# rpi-i2c.net
KiCad netlist of a schematic drawn in EAGLE
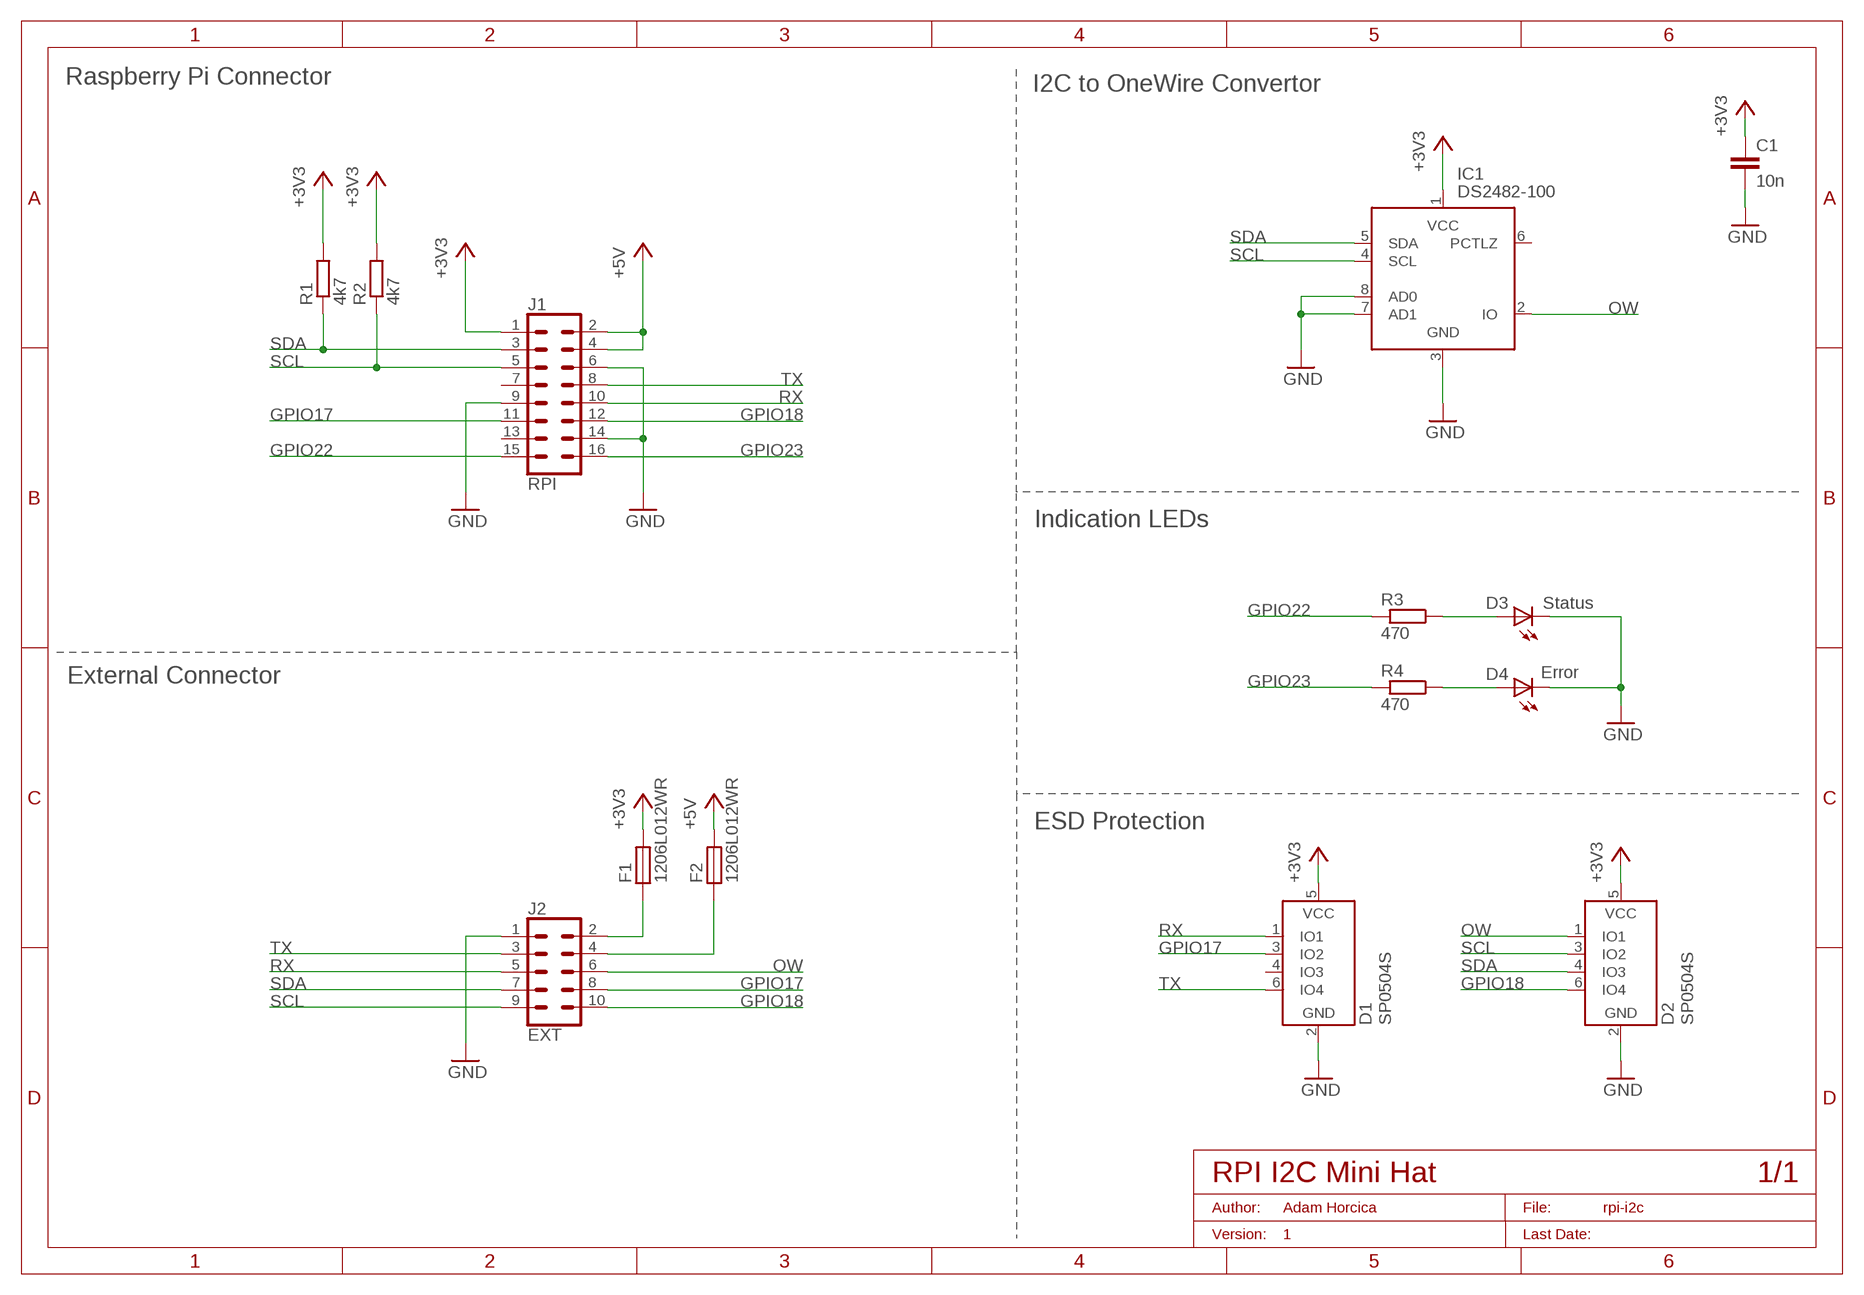
[diagram p0: schematic, sheet 1]

(export (version "E")
  (design (tool "Eeschema 10.0.6"))
  (components
    (comp (ref "C1")
      (value "10n")
      (footprint "eagle-import:C0805")
      (libsource (lib "eagle-import") (part "C-EUC0805"))
    )
    (comp (ref "D1")
      (value "SP0504S")
      (footprint "eagle-import:SOT23-6")
      (libsource (lib "eagle-import") (part "SP0504S"))
    )
    (comp (ref "D2")
      (value "SP0504S")
      (footprint "eagle-import:SOT23-6")
      (libsource (lib "eagle-import") (part "SP0504S"))
    )
    (comp (ref "D3")
      (value "LEDCHIPLED_0805")
      (footprint "eagle-import:CHIPLED_0805")
      (libsource (lib "eagle-import") (part "LEDCHIPLED_0805"))
    )
    (comp (ref "D4")
      (value "LEDCHIPLED_0805")
      (footprint "eagle-import:CHIPLED_0805")
      (libsource (lib "eagle-import") (part "LEDCHIPLED_0805"))
    )
    (comp (ref "F1")
      (value "1206L012WR")
      (footprint "eagle-import:C1206K")
      (fields (field (name "OC_FARNELL") "1596988"))
      (libsource (lib "eagle-import") (part "PTC1206L075/13.2WR"))
    )
    (comp (ref "F2")
      (value "1206L012WR")
      (footprint "eagle-import:C1206K")
      (fields (field (name "OC_FARNELL") "1596988"))
      (libsource (lib "eagle-import") (part "PTC1206L075/13.2WR"))
    )
    (comp (ref "IC1")
      (value "DS2482-100")
      (footprint "eagle-import:SO08")
      (libsource (lib "eagle-import") (part "DS2482-100"))
    )
    (comp (ref "J1")
      (value "RPI")
      (footprint "eagle-import:2X8-INVERSE")
      (libsource (lib "eagle-import") (part "CONN_08X2I"))
    )
    (comp (ref "J2")
      (value "EXT")
      (footprint "eagle-import:30310-5002HB")
      (libsource (lib "eagle-import") (part "CONN_05X2"))
    )
    (comp (ref "R1")
      (value "4k7")
      (footprint "eagle-import:R0603")
      (libsource (lib "eagle-import") (part "R-EU_R0603"))
    )
    (comp (ref "R2")
      (value "4k7")
      (footprint "eagle-import:R0603")
      (libsource (lib "eagle-import") (part "R-EU_R0603"))
    )
    (comp (ref "R3")
      (value "470")
      (footprint "eagle-import:R0603")
      (libsource (lib "eagle-import") (part "R-EU_R0603"))
    )
    (comp (ref "R4")
      (value "470")
      (footprint "eagle-import:R0603")
      (libsource (lib "eagle-import") (part "R-EU_R0603"))
    )
  )
  (nets
    (net (code "1") (name "+3V3") (class "Default")
      (node (ref "C1") (pin "1") (pinfunction "1_1") (pintype "passive"))
      (node (ref "D1") (pin "5") (pinfunction "VCC_5") (pintype "bidirectional"))
      (node (ref "D2") (pin "5") (pinfunction "VCC_5") (pintype "bidirectional"))
      (node (ref "F1") (pin "2") (pinfunction "2_2") (pintype "passive"))
      (node (ref "IC1") (pin "1") (pinfunction "VCC_1") (pintype "bidirectional"))
      (node (ref "J1") (pin "1") (pinfunction "1_1") (pintype "passive"))
      (node (ref "R1") (pin "2") (pinfunction "2_2") (pintype "passive"))
      (node (ref "R2") (pin "2") (pinfunction "2_2") (pintype "passive"))
    )
    (net (code "2") (name "+5V") (class "Default")
      (node (ref "F2") (pin "2") (pinfunction "2_2") (pintype "passive"))
      (node (ref "J1") (pin "2") (pinfunction "2_2") (pintype "passive"))
      (node (ref "J1") (pin "4") (pinfunction "4_4") (pintype "passive"))
    )
    (net (code "3") (name "/GPIO17") (class "Default")
      (node (ref "D1") (pin "3") (pinfunction "IO2_3") (pintype "bidirectional"))
      (node (ref "J1") (pin "11") (pinfunction "11_11") (pintype "passive"))
      (node (ref "J2") (pin "8") (pinfunction "8_8") (pintype "passive"))
    )
    (net (code "4") (name "/GPIO18") (class "Default")
      (node (ref "D2") (pin "6") (pinfunction "IO4_6") (pintype "bidirectional"))
      (node (ref "J1") (pin "12") (pinfunction "12_12") (pintype "passive"))
      (node (ref "J2") (pin "10") (pinfunction "10_10") (pintype "passive"))
    )
    (net (code "5") (name "/GPIO22") (class "Default")
      (node (ref "J1") (pin "15") (pinfunction "15_15") (pintype "passive"))
      (node (ref "R3") (pin "2") (pinfunction "2_2") (pintype "passive"))
    )
    (net (code "6") (name "/GPIO23") (class "Default")
      (node (ref "J1") (pin "16") (pinfunction "16_16") (pintype "passive"))
      (node (ref "R4") (pin "2") (pinfunction "2_2") (pintype "passive"))
    )
    (net (code "7") (name "/OW") (class "Default")
      (node (ref "D2") (pin "1") (pinfunction "IO1_1") (pintype "bidirectional"))
      (node (ref "IC1") (pin "2") (pinfunction "IO_2") (pintype "bidirectional"))
      (node (ref "J2") (pin "6") (pinfunction "6_6") (pintype "passive"))
    )
    (net (code "8") (name "/RX") (class "Default")
      (node (ref "D1") (pin "1") (pinfunction "IO1_1") (pintype "bidirectional"))
      (node (ref "J1") (pin "10") (pinfunction "10_10") (pintype "passive"))
      (node (ref "J2") (pin "5") (pinfunction "5_5") (pintype "passive"))
    )
    (net (code "9") (name "/SCL") (class "Default")
      (node (ref "D2") (pin "3") (pinfunction "IO2_3") (pintype "bidirectional"))
      (node (ref "IC1") (pin "4") (pinfunction "SCL_4") (pintype "bidirectional"))
      (node (ref "J1") (pin "5") (pinfunction "5_5") (pintype "passive"))
      (node (ref "J2") (pin "9") (pinfunction "9_9") (pintype "passive"))
      (node (ref "R2") (pin "1") (pinfunction "1_1") (pintype "passive"))
    )
    (net (code "10") (name "/SDA") (class "Default")
      (node (ref "D2") (pin "4") (pinfunction "IO3_4") (pintype "bidirectional"))
      (node (ref "IC1") (pin "5") (pinfunction "SDA_5") (pintype "bidirectional"))
      (node (ref "J1") (pin "3") (pinfunction "3_3") (pintype "passive"))
      (node (ref "J2") (pin "7") (pinfunction "7_7") (pintype "passive"))
      (node (ref "R1") (pin "1") (pinfunction "1_1") (pintype "passive"))
    )
    (net (code "11") (name "/TX") (class "Default")
      (node (ref "D1") (pin "6") (pinfunction "IO4_6") (pintype "bidirectional"))
      (node (ref "J1") (pin "8") (pinfunction "8_8") (pintype "passive"))
      (node (ref "J2") (pin "3") (pinfunction "3_3") (pintype "passive"))
    )
    (net (code "12") (name "GND") (class "Default")
      (node (ref "C1") (pin "2") (pinfunction "2_2") (pintype "passive"))
      (node (ref "D1") (pin "2") (pinfunction "GND_2") (pintype "bidirectional"))
      (node (ref "D2") (pin "2") (pinfunction "GND_2") (pintype "bidirectional"))
      (node (ref "D3") (pin "C") (pinfunction "C_C") (pintype "passive"))
      (node (ref "D4") (pin "C") (pinfunction "C_C") (pintype "passive"))
      (node (ref "IC1") (pin "3") (pinfunction "GND_3") (pintype "bidirectional"))
      (node (ref "IC1") (pin "7") (pinfunction "AD1_7") (pintype "bidirectional"))
      (node (ref "IC1") (pin "8") (pinfunction "AD0_8") (pintype "bidirectional"))
      (node (ref "J1") (pin "14") (pinfunction "14_14") (pintype "passive"))
      (node (ref "J1") (pin "6") (pinfunction "6_6") (pintype "passive"))
      (node (ref "J1") (pin "9") (pinfunction "9_9") (pintype "passive"))
      (node (ref "J2") (pin "1") (pinfunction "1_1") (pintype "passive"))
    )
    (net (code "13") (name "Net-(D3-PadA)") (class "Default")
      (node (ref "D3") (pin "A") (pinfunction "A_A") (pintype "passive"))
      (node (ref "R3") (pin "1") (pinfunction "1_1") (pintype "passive"))
    )
    (net (code "14") (name "Net-(D4-PadA)") (class "Default")
      (node (ref "D4") (pin "A") (pinfunction "A_A") (pintype "passive"))
      (node (ref "R4") (pin "1") (pinfunction "1_1") (pintype "passive"))
    )
    (net (code "15") (name "Net-(F1-Pad1)") (class "Default")
      (node (ref "F1") (pin "1") (pinfunction "1_1") (pintype "passive"))
      (node (ref "J2") (pin "2") (pinfunction "2_2") (pintype "passive"))
    )
    (net (code "16") (name "Net-(F2-Pad1)") (class "Default")
      (node (ref "F2") (pin "1") (pinfunction "1_1") (pintype "passive"))
      (node (ref "J2") (pin "4") (pinfunction "4_4") (pintype "passive"))
    )
    (net (code "17") (name "unconnected-(D1-IO3-Pad4)") (class "Default")
      (node (ref "D1") (pin "4") (pinfunction "IO3_4") (pintype "bidirectional"))
    )
    (net (code "18") (name "unconnected-(IC1-PCTLZ-Pad6)") (class "Default")
      (node (ref "IC1") (pin "6") (pinfunction "PCTLZ_6") (pintype "bidirectional"))
    )
    (net (code "19") (name "unconnected-(J1-Pad7)") (class "Default")
      (node (ref "J1") (pin "7") (pinfunction "7_7") (pintype "passive"))
    )
    (net (code "20") (name "unconnected-(J1-Pad13)") (class "Default")
      (node (ref "J1") (pin "13") (pinfunction "13_13") (pintype "passive"))
    )
  )
)
